# Mainboard_Power_Interface.net
KiCad netlist of a schematic drawn in Altium Designer
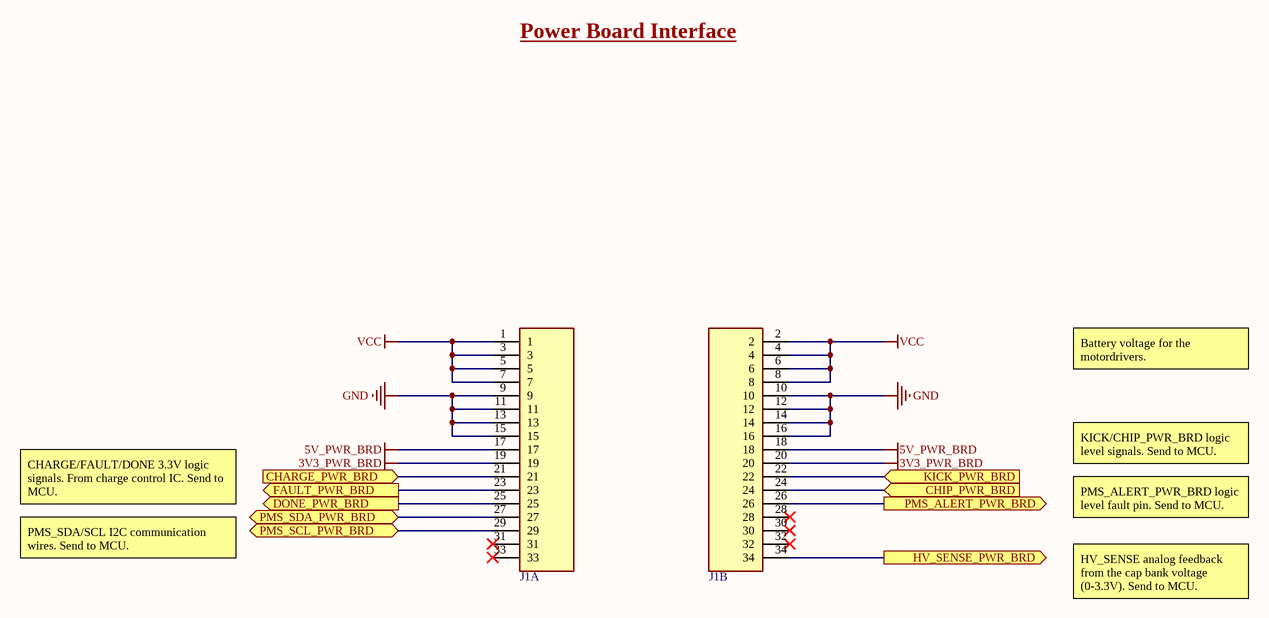
[diagram p0: Mainboard_Power_Interface.SchDoc]

(export (version "E")
  (design (tool "Eeschema 10.0.6"))
  (components
    (comp (ref "J1")
      (value "0.1\" Header Female 34")
      (footprint "SAMTEC-SSM-117-X-DV")
      (description "Female Header THRU 34POS 2ROW 0.1\" (2.54mm) pitch")
      (libsource (lib "AltiumLibraries") (part "CN HDR 34POS 2x17"))
    )
  )
  (nets
    (net (code "1") (name "/CHARGE_PWR_BRD") (class "Default")
      (node (ref "J1") (pin "21") (pinfunction "21_21") (pintype "passive"))
    )
    (net (code "2") (name "/CHIP_PWR_BRD") (class "Default")
      (node (ref "J1") (pin "24") (pinfunction "24_24") (pintype "passive"))
    )
    (net (code "3") (name "/DONE_PWR_BRD") (class "Default")
      (node (ref "J1") (pin "25") (pinfunction "25_25") (pintype "passive"))
    )
    (net (code "4") (name "/FAULT_PWR_BRD") (class "Default")
      (node (ref "J1") (pin "23") (pinfunction "23_23") (pintype "passive"))
    )
    (net (code "5") (name "/HV_SENSE_PWR_BRD") (class "Default")
      (node (ref "J1") (pin "34") (pinfunction "34_34") (pintype "passive"))
    )
    (net (code "6") (name "/KICK_PWR_BRD") (class "Default")
      (node (ref "J1") (pin "22") (pinfunction "22_22") (pintype "passive"))
    )
    (net (code "7") (name "/PMS_ALERT_PWR_BRD") (class "Default")
      (node (ref "J1") (pin "26") (pinfunction "26_26") (pintype "passive"))
    )
    (net (code "8") (name "/PMS_SCL_PWR_BRD") (class "Default")
      (node (ref "J1") (pin "29") (pinfunction "29_29") (pintype "passive"))
    )
    (net (code "9") (name "/PMS_SDA_PWR_BRD") (class "Default")
      (node (ref "J1") (pin "27") (pinfunction "27_27") (pintype "passive"))
    )
    (net (code "10") (name "3V3_PWR_BRD") (class "Default")
      (node (ref "J1") (pin "19") (pinfunction "19_19") (pintype "passive"))
      (node (ref "J1") (pin "20") (pinfunction "20_20") (pintype "passive"))
    )
    (net (code "11") (name "5V_PWR_BRD") (class "Default")
      (node (ref "J1") (pin "17") (pinfunction "17_17") (pintype "passive"))
      (node (ref "J1") (pin "18") (pinfunction "18_18") (pintype "passive"))
    )
    (net (code "12") (name "GND") (class "Default")
      (node (ref "J1") (pin "10") (pinfunction "10_10") (pintype "passive"))
      (node (ref "J1") (pin "11") (pinfunction "11_11") (pintype "passive"))
      (node (ref "J1") (pin "12") (pinfunction "12_12") (pintype "passive"))
      (node (ref "J1") (pin "13") (pinfunction "13_13") (pintype "passive"))
      (node (ref "J1") (pin "14") (pinfunction "14_14") (pintype "passive"))
      (node (ref "J1") (pin "15") (pinfunction "15_15") (pintype "passive"))
      (node (ref "J1") (pin "16") (pinfunction "16_16") (pintype "passive"))
      (node (ref "J1") (pin "9") (pinfunction "9_9") (pintype "passive"))
    )
    (net (code "13") (name "VCC") (class "Default")
      (node (ref "J1") (pin "1") (pinfunction "1_1") (pintype "passive"))
      (node (ref "J1") (pin "2") (pinfunction "2_2") (pintype "passive"))
      (node (ref "J1") (pin "3") (pinfunction "3_3") (pintype "passive"))
      (node (ref "J1") (pin "4") (pinfunction "4_4") (pintype "passive"))
      (node (ref "J1") (pin "5") (pinfunction "5_5") (pintype "passive"))
      (node (ref "J1") (pin "6") (pinfunction "6_6") (pintype "passive"))
      (node (ref "J1") (pin "7") (pinfunction "7_7") (pintype "passive"))
      (node (ref "J1") (pin "8") (pinfunction "8_8") (pintype "passive"))
    )
    (net (code "14") (name "unconnected-(J1-Pad28)") (class "Default")
      (node (ref "J1") (pin "28") (pinfunction "28_28") (pintype "passive+no_connect"))
    )
    (net (code "15") (name "unconnected-(J1-Pad30)") (class "Default")
      (node (ref "J1") (pin "30") (pinfunction "30_30") (pintype "passive+no_connect"))
    )
    (net (code "16") (name "unconnected-(J1-Pad31)") (class "Default")
      (node (ref "J1") (pin "31") (pinfunction "31_31") (pintype "passive+no_connect"))
    )
    (net (code "17") (name "unconnected-(J1-Pad32)") (class "Default")
      (node (ref "J1") (pin "32") (pinfunction "32_32") (pintype "passive+no_connect"))
    )
    (net (code "18") (name "unconnected-(J1-Pad33)") (class "Default")
      (node (ref "J1") (pin "33") (pinfunction "33_33") (pintype "passive+no_connect"))
    )
  )
)
